# Controller.net
KiCad netlist of a schematic drawn in Altium Designer
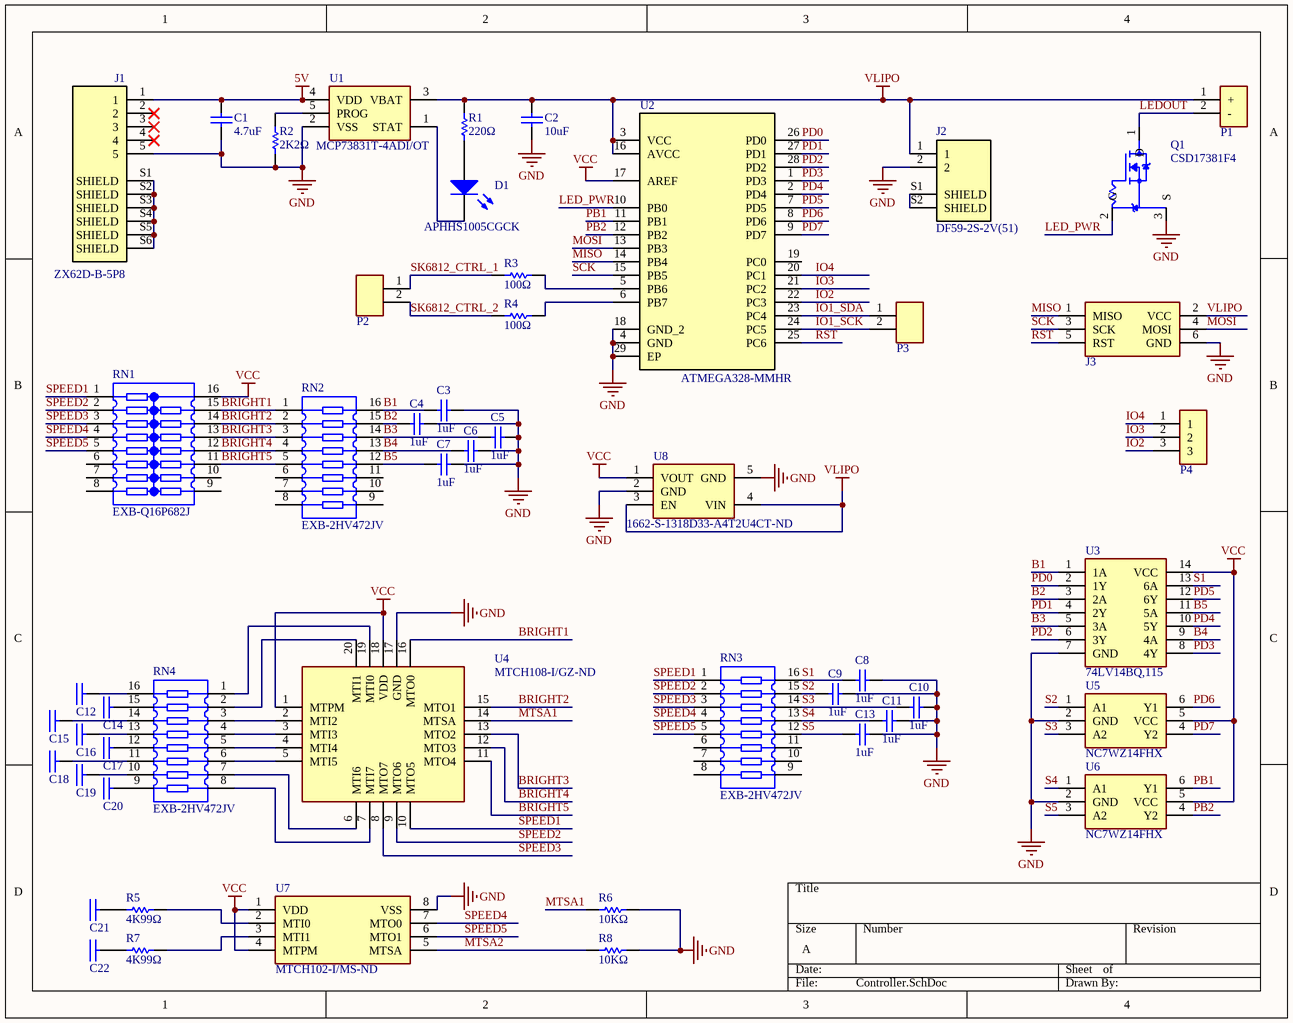
[diagram p0: Controller.SchDoc]

(export (version "E")
  (design (tool "Eeschema 10.0.6"))
  (components
    (comp (ref "C1")
      (value "4.7uF")
      (footprint "0603_CAP")
      (description "CAP CER 4.7UF 25V X5R 0603")
      (fields (field (name "PUBLISHER") "Altium Limited"))
      (libsource (lib "Capacitors_0603") (part "CAP_4U7_0603"))
    )
    (comp (ref "C2")
      (value "10uF")
      (footprint "0603_CAP")
      (description "CAP CER 10UF 10V X5R 0603")
      (fields (field (name "PUBLISHER") "Altium Limited"))
      (libsource (lib "Capacitors_0603") (part "CAP_10U_0603"))
    )
    (comp (ref "C3")
      (value "1uF")
      (footprint "0603_CAP")
      (description "CAP CER 1UF 50V X7R 0603")
      (fields (field (name "PUBLISHER") "Altium Limited"))
      (libsource (lib "Capacitors_0603") (part "CAP_1U_0603"))
    )
    (comp (ref "C4")
      (value "1uF")
      (footprint "0603_CAP")
      (description "CAP CER 1UF 50V X7R 0603")
      (fields (field (name "PUBLISHER") "Altium Limited"))
      (libsource (lib "Capacitors_0603") (part "CAP_1U_0603"))
    )
    (comp (ref "C5")
      (value "1uF")
      (footprint "0603_CAP")
      (description "CAP CER 1UF 50V X7R 0603")
      (fields (field (name "PUBLISHER") "Altium Limited"))
      (libsource (lib "Capacitors_0603") (part "CAP_1U_0603"))
    )
    (comp (ref "C6")
      (value "1uF")
      (footprint "0603_CAP")
      (description "CAP CER 1UF 50V X7R 0603")
      (fields (field (name "PUBLISHER") "Altium Limited"))
      (libsource (lib "Capacitors_0603") (part "CAP_1U_0603"))
    )
    (comp (ref "C7")
      (value "1uF")
      (footprint "0603_CAP")
      (description "CAP CER 1UF 50V X7R 0603")
      (fields (field (name "PUBLISHER") "Altium Limited"))
      (libsource (lib "Capacitors_0603") (part "CAP_1U_0603"))
    )
    (comp (ref "C8")
      (value "1uF")
      (footprint "0603_CAP")
      (description "CAP CER 1UF 50V X7R 0603")
      (fields (field (name "PUBLISHER") "Altium Limited"))
      (libsource (lib "Capacitors_0603") (part "CAP_1U_0603"))
    )
    (comp (ref "C9")
      (value "1uF")
      (footprint "0603_CAP")
      (description "CAP CER 1UF 50V X7R 0603")
      (fields (field (name "PUBLISHER") "Altium Limited"))
      (libsource (lib "Capacitors_0603") (part "CAP_1U_0603"))
    )
    (comp (ref "C10")
      (value "1uF")
      (footprint "0603_CAP")
      (description "CAP CER 1UF 50V X7R 0603")
      (fields (field (name "PUBLISHER") "Altium Limited"))
      (libsource (lib "Capacitors_0603") (part "CAP_1U_0603"))
    )
    (comp (ref "C11")
      (value "1uF")
      (footprint "0603_CAP")
      (description "CAP CER 1UF 50V X7R 0603")
      (fields (field (name "PUBLISHER") "Altium Limited"))
      (libsource (lib "Capacitors_0603") (part "CAP_1U_0603"))
    )
    (comp (ref "C12")
      (value "Human Body Model")
      (footprint "TOUCHSENSE_SLIDE1-END2")
      (description "Touch Sensor Pad, Slide Style 1")
      (fields (field (name "PUBLISHER") "Altium Limited"))
      (libsource (lib "Common Passives") (part "CAP_TOUCH_SLIDE1_END2"))
    )
    (comp (ref "C13")
      (value "1uF")
      (footprint "0603_CAP")
      (description "CAP CER 1UF 50V X7R 0603")
      (fields (field (name "PUBLISHER") "Altium Limited"))
      (libsource (lib "Capacitors_0603") (part "CAP_1U_0603"))
    )
    (comp (ref "C14")
      (value "Human Body Model")
      (footprint "TOUCHSENSE_SLIDE1")
      (description "Touch Sensor Pad, Slide Style 1")
      (fields (field (name "PUBLISHER") "Altium Limited"))
      (libsource (lib "Common Passives") (part "CAP_TOUCH_SLIDE1"))
    )
    (comp (ref "C15")
      (value "Human Body Model")
      (footprint "TOUCHSENSE_SLIDE1")
      (description "Touch Sensor Pad, Slide Style 1")
      (fields (field (name "PUBLISHER") "Altium Limited"))
      (libsource (lib "Common Passives") (part "CAP_TOUCH_SLIDE1"))
    )
    (comp (ref "C16")
      (value "Human Body Model")
      (footprint "TOUCHSENSE_SLIDE1")
      (description "Touch Sensor Pad, Slide Style 1")
      (fields (field (name "PUBLISHER") "Altium Limited"))
      (libsource (lib "Common Passives") (part "CAP_TOUCH_SLIDE1"))
    )
    (comp (ref "C17")
      (value "Human Body Model")
      (footprint "TOUCHSENSE_SLIDE1")
      (description "Touch Sensor Pad, Slide Style 1")
      (fields (field (name "PUBLISHER") "Altium Limited"))
      (libsource (lib "Common Passives") (part "CAP_TOUCH_SLIDE1"))
    )
    (comp (ref "C18")
      (value "Human Body Model")
      (footprint "TOUCHSENSE_SLIDE1")
      (description "Touch Sensor Pad, Slide Style 1")
      (fields (field (name "PUBLISHER") "Altium Limited"))
      (libsource (lib "Common Passives") (part "CAP_TOUCH_SLIDE1"))
    )
    (comp (ref "C19")
      (value "Human Body Model")
      (footprint "TOUCHSENSE_SLIDE1")
      (description "Touch Sensor Pad, Slide Style 1")
      (fields (field (name "PUBLISHER") "Altium Limited"))
      (libsource (lib "Common Passives") (part "CAP_TOUCH_SLIDE1"))
    )
    (comp (ref "C20")
      (value "Human Body Model")
      (footprint "TOUCHSENSE_SLIDE1")
      (description "Touch Sensor Pad, Slide Style 1")
      (fields (field (name "PUBLISHER") "Altium Limited"))
      (libsource (lib "Common Passives") (part "CAP_TOUCH_SLIDE1"))
    )
    (comp (ref "C21")
      (value "Human Body Model")
      (footprint "TOUCHSENSE_SLIDE1")
      (description "Touch Sensor Pad, Slide Style 1")
      (fields (field (name "PUBLISHER") "Altium Limited"))
      (libsource (lib "Common Passives") (part "CAP_TOUCH_SLIDE1"))
    )
    (comp (ref "C22")
      (value "Human Body Model")
      (footprint "TOUCHSENSE_SLIDE1-END1")
      (description "Touch Sensor Pad, Slide Style 1")
      (fields (field (name "PUBLISHER") "Altium Limited"))
      (libsource (lib "Common Passives") (part "CAP_TOUCH_SLIDE1_END1"))
    )
    (comp (ref "D1")
      (value "APHHS1005CGCK")
      (footprint "0402-LED-G")
      (description "LED GREEN CLEAR CHIP SMD")
      (libsource (lib "Diodes") (part "APHHS1005CGCK"))
    )
    (comp (ref "J1")
      (value "ZX62D-B-5P8")
      (footprint "Micro_USB")
      (description "SMD+DIP Micro USB; MICRO-B-SMD")
      (fields (field (name "MF") "Hirose"))
      (libsource (lib "Connectors") (part "MicroUSB"))
    )
    (comp (ref "J2")
      (value "DF59-2S-2V(51)")
      (footprint "SNAPBEE_DF59-2S-2V")
      (description "CONN SSL RCPT 2POS 2MM SOLDER")
      (libsource (lib "Connectors") (part "SNAPBEE_DF59-2S-2V"))
    )
    (comp (ref "J3")
      (value "6 Pin ISP Header")
      (footprint "CONN_ISP_TINY")
      (libsource (lib "Connectors") (part "ISP_TINY"))
    )
    (comp (ref "P1")
      (value "HEADER_1x2_POLAR")
      (footprint "PIN2")
      (description "Polarity")
      (libsource (lib "Connectors") (part "HEADER_1x2_POLAR"))
    )
    (comp (ref "P2")
      (value "HEADER_1x2")
      (footprint "PIN2")
      (libsource (lib "Connectors") (part "HEADER_1x2"))
    )
    (comp (ref "P3") (value "HEADER_1x2") (footprint "PIN2") (libsource (lib "") (part "HEADER_1x2_1")))
    (comp (ref "P4")
      (value "HEADER_1x3")
      (footprint "PIN3")
      (libsource (lib "Connectors") (part "HEADER_1x3"))
    )
    (comp (ref "Q1")
      (value "CSD17381F4")
      (footprint "Common Components:PICOSTAR-3")
      (description "MOSFET N-CH 30V 3.1A 3PICOSTAR")
      (fields (field (name "MF") "{'manufacturer': u'Texas Instruments'}"))
      (libsource (lib "Transistors") (part "CSD17381F4"))
    )
    (comp (ref "R1")
      (value "220Ω")
      (footprint "0603_RES")
      (description "RES SMD 220 OHM 1% 1/10W 0603")
      (fields (field (name "PUBLISHER") "Altium Limited"))
      (libsource (lib "Resistors_0603") (part "RES_220R_0603"))
    )
    (comp (ref "R2")
      (value "2K2Ω")
      (footprint "0603_RES")
      (description "RES SMD 2.2K OHM 1% 1/10W 0603")
      (fields (field (name "PUBLISHER") "Altium Limited"))
      (libsource (lib "Resistors_0603") (part "RES_2K2_0603"))
    )
    (comp (ref "R3")
      (value "100Ω")
      (footprint "0603_RES")
      (description "RES SMD 100 OHM 1% 1/10W 0603")
      (fields (field (name "PUBLISHER") "Altium Limited"))
      (libsource (lib "Resistors_0603") (part "RES_100R_0603"))
    )
    (comp (ref "R4")
      (value "100Ω")
      (footprint "0603_RES")
      (description "RES SMD 100 OHM 1% 1/10W 0603")
      (fields (field (name "PUBLISHER") "Altium Limited"))
      (libsource (lib "Resistors_0603") (part "RES_100R_0603"))
    )
    (comp (ref "R5")
      (value "4K99Ω")
      (footprint "0603_RES")
      (description "RES SMD 4.99K OHM 1% 1/10W 0603")
      (fields (field (name "PUBLISHER") "Altium Limited"))
      (libsource (lib "Resistors_0603") (part "RES_4K99_0603"))
    )
    (comp (ref "R6")
      (value "10KΩ")
      (footprint "0603_RES")
      (description "RES SMD 10K OHM 1% 1/10W 0603")
      (fields (field (name "PUBLISHER") "Altium Limited"))
      (libsource (lib "Resistors_0603") (part "RES_10K_0603"))
    )
    (comp (ref "R7")
      (value "4K99Ω")
      (footprint "0603_RES")
      (description "RES SMD 4.99K OHM 1% 1/10W 0603")
      (fields (field (name "PUBLISHER") "Altium Limited"))
      (libsource (lib "Resistors_0603") (part "RES_4K99_0603"))
    )
    (comp (ref "R8")
      (value "10KΩ")
      (footprint "0603_RES")
      (description "RES SMD 10K OHM 1% 1/10W 0603")
      (fields (field (name "PUBLISHER") "Altium Limited"))
      (libsource (lib "Resistors_0603") (part "RES_10K_0603"))
    )
    (comp (ref "RN1")
      (value "EXB-Q16P682J")
      (footprint "Common Components:RES-ARRAY-16_EXB")
      (description "RES ARRAY 15 RES 6.8K OHM 1506")
      (fields (field (name "MF") "{'manufacturer': u'Panasonic'}"))
      (libsource (lib "Common Passives") (part "EXB-Q16P682J"))
    )
    (comp (ref "RN2")
      (value "EXB-2HV472JV")
      (footprint "Common Components:RES-ARRAY-16_EXB")
      (description "RES ARRAY 8 RES 4.7K OHM 1506")
      (fields (field (name "MF") "{'manufacturer': u'Panasonic'}") (field (name "MP") "EXB-Q16P682J"))
      (libsource (lib "Common Passives") (part "EXB-2HV472JV"))
    )
    (comp (ref "RN3")
      (value "EXB-2HV472JV")
      (footprint "Common Components:RES-ARRAY-16_EXB")
      (description "RES ARRAY 8 RES 4.7K OHM 1506")
      (fields (field (name "MF") "{'manufacturer': u'Panasonic'}") (field (name "MP") "EXB-Q16P682J"))
      (libsource (lib "Common Passives") (part "EXB-2HV472JV"))
    )
    (comp (ref "RN4")
      (value "EXB-2HV472JV")
      (footprint "Common Components:RES-ARRAY-16_EXB")
      (description "RES ARRAY 8 RES 4.7K OHM 1506")
      (fields (field (name "MF") "{'manufacturer': u'Panasonic'}") (field (name "MP") "EXB-Q16P682J"))
      (libsource (lib "") (part "EXB-2HV472JV_1"))
    )
    (comp (ref "U1")
      (value "MCP73831T-4ADI/OT")
      (footprint "Common Components:SOT-23-5-N")
      (description "IC BATT CNTL LI-ION 1CEL SOT23-5")
      (fields (field (name "MF") "{'manufacturer': u'Microchip'}"))
      (libsource (lib "Common ICs") (part "MCP73831T-4ADI/OT"))
    )
    (comp (ref "U2")
      (value "ATMEGA328-MMHR")
      (footprint "Common Components:QFN-28_4x4")
      (description "IC MCU 8BIT 32KB FLASH 28VQFN")
      (fields (field (name "MF") "Microchip") (field (name "MP") "ATMEGA328P-PU"))
      (libsource (lib "Microcontrollers") (part "ATMEGA328-MMHR"))
    )
    (comp (ref "U3")
      (value "74LV14BQ,115")
      (footprint "DHVQFN-14")
      (description "IC INVERTER 6CH 6-INP 14DHVQFN")
      (libsource (lib "74xxChips") (part "74LV14BQ,115"))
    )
    (comp (ref "U4")
      (value "MTCH108-I/GZ")
      (footprint "UQFN-20_4x4")
      (description "IC PROXIMITY DETECTOR 20UQFN")
      (fields (field (name "SUPPLIER PART NUMBER 1") "MTCH108-I/GZ-ND"))
      (libsource (lib "Common ICs") (part "MTCH108-I/GZ"))
    )
    (comp (ref "U5")
      (value "NC7WZ14FHX")
      (footprint "MICROPAK2")
      (description "IC INVERTER 2CH 2-INP 6MICROPAK2")
      (libsource (lib "74xxChips") (part "NC7WZ14FHX"))
    )
    (comp (ref "U6")
      (value "NC7WZ14FHX")
      (footprint "MICROPAK2")
      (description "IC INVERTER 2CH 2-INP 6MICROPAK2")
      (libsource (lib "74xxChips") (part "NC7WZ14FHX"))
    )
    (comp (ref "U7")
      (value "MTCH102-I/MS")
      (footprint "MSOP-8")
      (description "IC PROXIMITY DETECTOR 8MSOP")
      (fields (field (name "SUPPLIER PART NUMBER 1") "MTCH102-I/MS-ND"))
      (libsource (lib "Common ICs") (part "MTCH102-I/MS"))
    )
    (comp (ref "U8")
      (value "S-1318D33-A4T2U4")
      (footprint "HSNT-4-B")
      (description "IC REG LINEAR 3.3V 100MA HSNT4-B")
      (fields (field (name "SUPPLIER PART NUMBER 1") "1662-S-1318D33-A4T2U4CT-ND"))
      (libsource (lib "Common ICs") (part "S-1318D33-A4T2U4"))
    )
  )
  (nets
    (net (code "1") (name "/B1") (class "Default")
      (node (ref "C3") (pin "2") (pinfunction "2_2") (pintype "passive"))
      (node (ref "RN2") (pin "16") (pinfunction "16_16") (pintype "passive"))
      (node (ref "U3") (pin "1") (pinfunction "1A_1") (pintype "passive"))
    )
    (net (code "2") (name "/B2") (class "Default")
      (node (ref "C4") (pin "2") (pinfunction "2_2") (pintype "passive"))
      (node (ref "RN2") (pin "15") (pinfunction "15_15") (pintype "passive"))
      (node (ref "U3") (pin "3") (pinfunction "2A_3") (pintype "passive"))
    )
    (net (code "3") (name "/B3") (class "Default")
      (node (ref "C5") (pin "2") (pinfunction "2_2") (pintype "passive"))
      (node (ref "RN2") (pin "14") (pinfunction "14_14") (pintype "passive"))
      (node (ref "U3") (pin "5") (pinfunction "3A_5") (pintype "passive"))
    )
    (net (code "4") (name "/B4") (class "Default")
      (node (ref "C6") (pin "2") (pinfunction "2_2") (pintype "passive"))
      (node (ref "RN2") (pin "13") (pinfunction "13_13") (pintype "passive"))
      (node (ref "U3") (pin "9") (pinfunction "4A_9") (pintype "passive"))
    )
    (net (code "5") (name "/B5") (class "Default")
      (node (ref "C7") (pin "1") (pinfunction "1_1") (pintype "passive"))
      (node (ref "RN2") (pin "12") (pinfunction "12_12") (pintype "passive"))
      (node (ref "U3") (pin "11") (pinfunction "5A_11") (pintype "passive"))
    )
    (net (code "6") (name "/BRIGHT1") (class "Default")
      (node (ref "RN1") (pin "15") (pinfunction "15_15") (pintype "passive"))
      (node (ref "RN2") (pin "1") (pinfunction "1_1") (pintype "passive"))
      (node (ref "U4") (pin "16") (pinfunction "MTO0_16") (pintype "passive"))
    )
    (net (code "7") (name "/BRIGHT2") (class "Default")
      (node (ref "RN1") (pin "14") (pinfunction "14_14") (pintype "passive"))
      (node (ref "RN2") (pin "2") (pinfunction "2_2") (pintype "passive"))
      (node (ref "U4") (pin "15") (pinfunction "MTO1_15") (pintype "passive"))
    )
    (net (code "8") (name "/BRIGHT3") (class "Default")
      (node (ref "RN1") (pin "13") (pinfunction "13_13") (pintype "passive"))
      (node (ref "RN2") (pin "3") (pinfunction "3_3") (pintype "passive"))
      (node (ref "U4") (pin "13") (pinfunction "MTO2_13") (pintype "passive"))
    )
    (net (code "9") (name "/BRIGHT4") (class "Default")
      (node (ref "RN1") (pin "12") (pinfunction "12_12") (pintype "passive"))
      (node (ref "RN2") (pin "4") (pinfunction "4_4") (pintype "passive"))
      (node (ref "U4") (pin "12") (pinfunction "MTO3_12") (pintype "passive"))
    )
    (net (code "10") (name "/BRIGHT5") (class "Default")
      (node (ref "RN1") (pin "11") (pinfunction "11_11") (pintype "passive"))
      (node (ref "RN2") (pin "5") (pinfunction "5_5") (pintype "passive"))
      (node (ref "U4") (pin "11") (pinfunction "MTO4_11") (pintype "passive"))
    )
    (net (code "11") (name "/IO1_SCK") (class "Default")
      (node (ref "P3") (pin "2") (pinfunction "-_2") (pintype "passive"))
      (node (ref "U2") (pin "24") (pinfunction "PC5_24") (pintype "passive"))
    )
    (net (code "12") (name "/IO1_SDA") (class "Default")
      (node (ref "P3") (pin "1") (pinfunction "+_1") (pintype "passive"))
      (node (ref "U2") (pin "23") (pinfunction "PC4_23") (pintype "passive"))
    )
    (net (code "13") (name "/IO2") (class "Default")
      (node (ref "P4") (pin "3") (pinfunction "3_3") (pintype "passive"))
      (node (ref "U2") (pin "22") (pinfunction "PC3_22") (pintype "passive"))
    )
    (net (code "14") (name "/IO3") (class "Default")
      (node (ref "P4") (pin "2") (pinfunction "2_2") (pintype "passive"))
      (node (ref "U2") (pin "21") (pinfunction "PC2_21") (pintype "passive"))
    )
    (net (code "15") (name "/IO4") (class "Default")
      (node (ref "P4") (pin "1") (pinfunction "1_1") (pintype "passive"))
      (node (ref "U2") (pin "20") (pinfunction "PC1_20") (pintype "passive"))
    )
    (net (code "16") (name "/LEDOUT") (class "Default")
      (node (ref "P1") (pin "2") (pinfunction "-_2") (pintype "passive"))
      (node (ref "Q1") (pin "1") (pinfunction "D_1") (pintype "passive"))
    )
    (net (code "17") (name "/LED_PWR") (class "Default")
      (node (ref "Q1") (pin "2") (pinfunction "G_2") (pintype "passive"))
      (node (ref "U2") (pin "10") (pinfunction "PB0_10") (pintype "passive"))
    )
    (net (code "18") (name "/MISO") (class "Default")
      (node (ref "J3") (pin "1") (pinfunction "MISO_1") (pintype "passive"))
      (node (ref "U2") (pin "14") (pinfunction "PB4_14") (pintype "passive"))
    )
    (net (code "19") (name "/MOSI") (class "Default")
      (node (ref "J3") (pin "4") (pinfunction "MOSI_4") (pintype "passive"))
      (node (ref "U2") (pin "13") (pinfunction "PB3_13") (pintype "passive"))
    )
    (net (code "20") (name "/MTSA1") (class "Default")
      (node (ref "R6") (pin "2") (pinfunction "2_2") (pintype "passive"))
      (node (ref "U4") (pin "14") (pinfunction "MTSA_14") (pintype "passive"))
    )
    (net (code "21") (name "/MTSA2") (class "Default")
      (node (ref "R8") (pin "1") (pinfunction "1_1") (pintype "passive"))
      (node (ref "U7") (pin "5") (pinfunction "MTSA_5") (pintype "passive"))
    )
    (net (code "22") (name "/PB1") (class "Default")
      (node (ref "U2") (pin "11") (pinfunction "PB1_11") (pintype "passive"))
      (node (ref "U6") (pin "6") (pinfunction "Y1_6") (pintype "passive"))
    )
    (net (code "23") (name "/PB2") (class "Default")
      (node (ref "U2") (pin "12") (pinfunction "PB2_12") (pintype "passive"))
      (node (ref "U6") (pin "4") (pinfunction "Y2_4") (pintype "passive"))
    )
    (net (code "24") (name "/PD0") (class "Default")
      (node (ref "U2") (pin "26") (pinfunction "PD0_26") (pintype "passive"))
      (node (ref "U3") (pin "2") (pinfunction "1Y_2") (pintype "passive"))
    )
    (net (code "25") (name "/PD1") (class "Default")
      (node (ref "U2") (pin "27") (pinfunction "PD1_27") (pintype "passive"))
      (node (ref "U3") (pin "4") (pinfunction "2Y_4") (pintype "passive"))
    )
    (net (code "26") (name "/PD2") (class "Default")
      (node (ref "U2") (pin "28") (pinfunction "PD2_28") (pintype "passive"))
      (node (ref "U3") (pin "6") (pinfunction "3Y_6") (pintype "passive"))
    )
    (net (code "27") (name "/PD3") (class "Default")
      (node (ref "U2") (pin "1") (pinfunction "PD3_1") (pintype "passive"))
      (node (ref "U3") (pin "8") (pinfunction "4Y_8") (pintype "passive"))
    )
    (net (code "28") (name "/PD4") (class "Default")
      (node (ref "U2") (pin "2") (pinfunction "PD4_2") (pintype "passive"))
      (node (ref "U3") (pin "10") (pinfunction "5Y_10") (pintype "passive"))
    )
    (net (code "29") (name "/PD5") (class "Default")
      (node (ref "U2") (pin "7") (pinfunction "PD5_7") (pintype "passive"))
      (node (ref "U3") (pin "12") (pinfunction "6Y_12") (pintype "passive"))
    )
    (net (code "30") (name "/PD6") (class "Default")
      (node (ref "U2") (pin "8") (pinfunction "PD6_8") (pintype "passive"))
      (node (ref "U5") (pin "6") (pinfunction "Y1_6") (pintype "passive"))
    )
    (net (code "31") (name "/PD7") (class "Default")
      (node (ref "U2") (pin "9") (pinfunction "PD7_9") (pintype "passive"))
      (node (ref "U5") (pin "4") (pinfunction "Y2_4") (pintype "passive"))
    )
    (net (code "32") (name "/RST") (class "Default")
      (node (ref "J3") (pin "5") (pinfunction "RST_5") (pintype "passive"))
      (node (ref "U2") (pin "25") (pinfunction "PC6_25") (pintype "passive"))
    )
    (net (code "33") (name "/S1") (class "Default")
      (node (ref "C8") (pin "2") (pinfunction "2_2") (pintype "passive"))
      (node (ref "RN3") (pin "16") (pinfunction "16_16") (pintype "passive"))
      (node (ref "U3") (pin "13") (pinfunction "6A_13") (pintype "passive"))
    )
    (net (code "34") (name "/S2") (class "Default")
      (node (ref "C9") (pin "2") (pinfunction "2_2") (pintype "passive"))
      (node (ref "RN3") (pin "15") (pinfunction "15_15") (pintype "passive"))
      (node (ref "U5") (pin "1") (pinfunction "A1_1") (pintype "passive"))
    )
    (net (code "35") (name "/S3") (class "Default")
      (node (ref "C10") (pin "2") (pinfunction "2_2") (pintype "passive"))
      (node (ref "RN3") (pin "14") (pinfunction "14_14") (pintype "passive"))
      (node (ref "U5") (pin "3") (pinfunction "A2_3") (pintype "passive"))
    )
    (net (code "36") (name "/S4") (class "Default")
      (node (ref "C11") (pin "2") (pinfunction "2_2") (pintype "passive"))
      (node (ref "RN3") (pin "13") (pinfunction "13_13") (pintype "passive"))
      (node (ref "U6") (pin "1") (pinfunction "A1_1") (pintype "passive"))
    )
    (net (code "37") (name "/S5") (class "Default")
      (node (ref "C13") (pin "1") (pinfunction "1_1") (pintype "passive"))
      (node (ref "RN3") (pin "12") (pinfunction "12_12") (pintype "passive"))
      (node (ref "U6") (pin "3") (pinfunction "A2_3") (pintype "passive"))
    )
    (net (code "38") (name "/SCK") (class "Default")
      (node (ref "J3") (pin "3") (pinfunction "SCK_3") (pintype "passive"))
      (node (ref "U2") (pin "15") (pinfunction "PB5_15") (pintype "passive"))
    )
    (net (code "39") (name "/SK6812_CTRL_1") (class "Default")
      (node (ref "P2") (pin "1") (pinfunction "+_1") (pintype "passive"))
      (node (ref "R3") (pin "1") (pinfunction "1_1") (pintype "passive"))
    )
    (net (code "40") (name "/SK6812_CTRL_2") (class "Default")
      (node (ref "P2") (pin "2") (pinfunction "-_2") (pintype "passive"))
      (node (ref "R4") (pin "1") (pinfunction "1_1") (pintype "passive"))
    )
    (net (code "41") (name "/SPEED1") (class "Default")
      (node (ref "RN1") (pin "1") (pinfunction "1_1") (pintype "passive"))
      (node (ref "RN3") (pin "1") (pinfunction "1_1") (pintype "passive"))
      (node (ref "U4") (pin "10") (pinfunction "MTO5_10") (pintype "passive"))
    )
    (net (code "42") (name "/SPEED2") (class "Default")
      (node (ref "RN1") (pin "2") (pinfunction "2_2") (pintype "passive"))
      (node (ref "RN3") (pin "2") (pinfunction "2_2") (pintype "passive"))
      (node (ref "U4") (pin "9") (pinfunction "MTO6_9") (pintype "passive"))
    )
    (net (code "43") (name "/SPEED3") (class "Default")
      (node (ref "RN1") (pin "3") (pinfunction "3_3") (pintype "passive"))
      (node (ref "RN3") (pin "3") (pinfunction "3_3") (pintype "passive"))
      (node (ref "U4") (pin "8") (pinfunction "MTO7_8") (pintype "passive"))
    )
    (net (code "44") (name "/SPEED4") (class "Default")
      (node (ref "RN1") (pin "4") (pinfunction "4_4") (pintype "passive"))
      (node (ref "RN3") (pin "4") (pinfunction "4_4") (pintype "passive"))
      (node (ref "U7") (pin "7") (pinfunction "MTO0_7") (pintype "passive"))
    )
    (net (code "45") (name "/SPEED5") (class "Default")
      (node (ref "RN1") (pin "5") (pinfunction "5_5") (pintype "passive"))
      (node (ref "RN3") (pin "5") (pinfunction "5_5") (pintype "passive"))
      (node (ref "U7") (pin "6") (pinfunction "MTO1_6") (pintype "passive"))
    )
    (net (code "46") (name "5V") (class "Default")
      (node (ref "C1") (pin "2") (pinfunction "2_2") (pintype "passive"))
      (node (ref "J1") (pin "1") (pinfunction "1_1") (pintype "power_in"))
      (node (ref "U1") (pin "4") (pinfunction "VDD_4") (pintype "passive"))
    )
    (net (code "47") (name "GND") (class "Default")
      (node (ref "C1") (pin "1") (pinfunction "1_1") (pintype "passive"))
      (node (ref "C10") (pin "1") (pinfunction "1_1") (pintype "passive"))
      (node (ref "C11") (pin "1") (pinfunction "1_1") (pintype "passive"))
      (node (ref "C13") (pin "2") (pinfunction "2_2") (pintype "passive"))
      (node (ref "C2") (pin "1") (pinfunction "1_1") (pintype "passive"))
      (node (ref "C3") (pin "1") (pinfunction "1_1") (pintype "passive"))
      (node (ref "C4") (pin "1") (pinfunction "1_1") (pintype "passive"))
      (node (ref "C5") (pin "1") (pinfunction "1_1") (pintype "passive"))
      (node (ref "C6") (pin "1") (pinfunction "1_1") (pintype "passive"))
      (node (ref "C7") (pin "2") (pinfunction "2_2") (pintype "passive"))
      (node (ref "C8") (pin "1") (pinfunction "1_1") (pintype "passive"))
      (node (ref "C9") (pin "1") (pinfunction "1_1") (pintype "passive"))
      (node (ref "J1") (pin "5") (pinfunction "5_5") (pintype "passive"))
      (node (ref "J2") (pin "2") (pinfunction "2_2") (pintype "passive"))
      (node (ref "J3") (pin "6") (pinfunction "GND_6") (pintype "passive"))
      (node (ref "Q1") (pin "3") (pinfunction "S_3") (pintype "passive"))
      (node (ref "R2") (pin "1") (pinfunction "1_1") (pintype "passive"))
      (node (ref "R6") (pin "1") (pinfunction "1_1") (pintype "passive"))
      (node (ref "R8") (pin "2") (pinfunction "2_2") (pintype "passive"))
      (node (ref "U1") (pin "2") (pinfunction "VSS_2") (pintype "passive"))
      (node (ref "U2") (pin "18") (pinfunction "GND_2_18") (pintype "passive"))
      (node (ref "U2") (pin "29") (pinfunction "EP_29") (pintype "passive"))
      (node (ref "U2") (pin "4") (pinfunction "GND_4") (pintype "passive"))
      (node (ref "U3") (pin "7") (pinfunction "GND_7") (pintype "passive"))
      (node (ref "U4") (pin "17") (pinfunction "GND_17") (pintype "passive"))
      (node (ref "U5") (pin "2") (pinfunction "GND_2") (pintype "passive"))
      (node (ref "U6") (pin "2") (pinfunction "GND_2") (pintype "passive"))
      (node (ref "U7") (pin "8") (pinfunction "VSS_8") (pintype "passive"))
      (node (ref "U8") (pin "2") (pinfunction "GND_2") (pintype "passive"))
      (node (ref "U8") (pin "5") (pinfunction "GND_5") (pintype "passive"))
    )
    (net (code "48") (name "Net-(C12-Pad1)") (class "Default")
      (node (ref "C12") (pin "1") (pinfunction "1_1") (pintype "passive"))
      (node (ref "RN4") (pin "16") (pinfunction "16_16") (pintype "passive"))
    )
    (net (code "49") (name "Net-(C14-Pad1)") (class "Default")
      (node (ref "C14") (pin "1") (pinfunction "1_1") (pintype "passive"))
      (node (ref "RN4") (pin "15") (pinfunction "15_15") (pintype "passive"))
    )
    (net (code "50") (name "Net-(C15-Pad1)") (class "Default")
      (node (ref "C15") (pin "1") (pinfunction "1_1") (pintype "passive"))
      (node (ref "RN4") (pin "14") (pinfunction "14_14") (pintype "passive"))
    )
    (net (code "51") (name "Net-(C16-Pad1)") (class "Default")
      (node (ref "C16") (pin "1") (pinfunction "1_1") (pintype "passive"))
      (node (ref "RN4") (pin "13") (pinfunction "13_13") (pintype "passive"))
    )
    (net (code "52") (name "Net-(C17-Pad1)") (class "Default")
      (node (ref "C17") (pin "1") (pinfunction "1_1") (pintype "passive"))
      (node (ref "RN4") (pin "12") (pinfunction "12_12") (pintype "passive"))
    )
    (net (code "53") (name "Net-(C18-Pad1)") (class "Default")
      (node (ref "C18") (pin "1") (pinfunction "1_1") (pintype "passive"))
      (node (ref "RN4") (pin "11") (pinfunction "11_11") (pintype "passive"))
    )
    (net (code "54") (name "Net-(C19-Pad1)") (class "Default")
      (node (ref "C19") (pin "1") (pinfunction "1_1") (pintype "passive"))
      (node (ref "RN4") (pin "10") (pinfunction "10_10") (pintype "passive"))
    )
    (net (code "55") (name "Net-(C20-Pad1)") (class "Default")
      (node (ref "C20") (pin "1") (pinfunction "1_1") (pintype "passive"))
      (node (ref "RN4") (pin "9") (pinfunction "9_9") (pintype "passive"))
    )
    (net (code "56") (name "Net-(C21-Pad1)") (class "Default")
      (node (ref "C21") (pin "1") (pinfunction "1_1") (pintype "passive"))
      (node (ref "R5") (pin "1") (pinfunction "1_1") (pintype "passive"))
    )
    (net (code "57") (name "Net-(C22-Pad1)") (class "Default")
      (node (ref "C22") (pin "1") (pinfunction "1_1") (pintype "passive"))
      (node (ref "R7") (pin "1") (pinfunction "1_1") (pintype "passive"))
    )
    (net (code "58") (name "Net-(D1-A)") (class "Default")
      (node (ref "D1") (pin "2") (pinfunction "A_2") (pintype "passive"))
      (node (ref "R1") (pin "1") (pinfunction "1_1") (pintype "passive"))
    )
    (net (code "59") (name "Net-(D1-K)") (class "Default")
      (node (ref "D1") (pin "1") (pinfunction "K_1") (pintype "passive"))
      (node (ref "U1") (pin "1") (pinfunction "STAT_1") (pintype "passive"))
    )
    (net (code "60") (name "Net-(J1-SHIELD-PadS1)") (class "Default")
      (node (ref "J1") (pin "S1") (pinfunction "SHIELD_S1") (pintype "passive"))
      (node (ref "J1") (pin "S2") (pinfunction "SHIELD_S2") (pintype "passive"))
      (node (ref "J1") (pin "S3") (pinfunction "SHIELD_S3") (pintype "passive"))
      (node (ref "J1") (pin "S4") (pinfunction "SHIELD_S4") (pintype "passive"))
      (node (ref "J1") (pin "S5") (pinfunction "SHIELD_S5") (pintype "passive"))
      (node (ref "J1") (pin "S6") (pinfunction "SHIELD_S6") (pintype "passive"))
    )
    (net (code "61") (name "Net-(J2-SHIELD-PadS1)") (class "Default")
      (node (ref "J2") (pin "S1") (pinfunction "SHIELD_S1") (pintype "passive"))
      (node (ref "J2") (pin "S2") (pinfunction "SHIELD_S2") (pintype "passive"))
    )
    (net (code "62") (name "Net-(U1-PROG)") (class "Default")
      (node (ref "R2") (pin "2") (pinfunction "2_2") (pintype "passive"))
      (node (ref "U1") (pin "5") (pinfunction "PROG_5") (pintype "passive"))
    )
    (net (code "63") (name "Net-(U2-PB6)") (class "Default")
      (node (ref "R3") (pin "2") (pinfunction "2_2") (pintype "passive"))
      (node (ref "U2") (pin "5") (pinfunction "PB6_5") (pintype "passive"))
    )
    (net (code "64") (name "Net-(U2-PB7)") (class "Default")
      (node (ref "R4") (pin "2") (pinfunction "2_2") (pintype "passive"))
      (node (ref "U2") (pin "6") (pinfunction "PB7_6") (pintype "passive"))
    )
    (net (code "65") (name "Net-(U4-MTI0)") (class "Default")
      (node (ref "RN4") (pin "1") (pinfunction "1_1") (pintype "passive"))
      (node (ref "U4") (pin "19") (pinfunction "MTI0_19") (pintype "passive"))
    )
    (net (code "66") (name "Net-(U4-MTI1)") (class "Default")
      (node (ref "RN4") (pin "2") (pinfunction "2_2") (pintype "passive"))
      (node (ref "U4") (pin "20") (pinfunction "MTI1_20") (pintype "passive"))
    )
    (net (code "67") (name "Net-(U4-MTI2)") (class "Default")
      (node (ref "RN4") (pin "3") (pinfunction "3_3") (pintype "passive"))
      (node (ref "U4") (pin "2") (pinfunction "MTI2_2") (pintype "passive"))
    )
    (net (code "68") (name "Net-(U4-MTI3)") (class "Default")
      (node (ref "RN4") (pin "4") (pinfunction "4_4") (pintype "passive"))
      (node (ref "U4") (pin "3") (pinfunction "MTI3_3") (pintype "passive"))
    )
    (net (code "69") (name "Net-(U4-MTI4)") (class "Default")
      (node (ref "RN4") (pin "5") (pinfunction "5_5") (pintype "passive"))
      (node (ref "U4") (pin "4") (pinfunction "MTI4_4") (pintype "passive"))
    )
    (net (code "70") (name "Net-(U4-MTI5)") (class "Default")
      (node (ref "RN4") (pin "6") (pinfunction "6_6") (pintype "passive"))
      (node (ref "U4") (pin "5") (pinfunction "MTI5_5") (pintype "passive"))
    )
    (net (code "71") (name "Net-(U4-MTI6)") (class "Default")
      (node (ref "RN4") (pin "7") (pinfunction "7_7") (pintype "passive"))
      (node (ref "U4") (pin "6") (pinfunction "MTI6_6") (pintype "passive"))
    )
    (net (code "72") (name "Net-(U4-MTI7)") (class "Default")
      (node (ref "RN4") (pin "8") (pinfunction "8_8") (pintype "passive"))
      (node (ref "U4") (pin "7") (pinfunction "MTI7_7") (pintype "passive"))
    )
    (net (code "73") (name "Net-(U7-MTI0)") (class "Default")
      (node (ref "R5") (pin "2") (pinfunction "2_2") (pintype "passive"))
      (node (ref "U7") (pin "2") (pinfunction "MTI0_2") (pintype "passive"))
    )
    (net (code "74") (name "Net-(U7-MTI1)") (class "Default")
      (node (ref "R7") (pin "2") (pinfunction "2_2") (pintype "passive"))
      (node (ref "U7") (pin "3") (pinfunction "MTI1_3") (pintype "passive"))
    )
    (net (code "75") (name "VCC") (class "Default")
      (node (ref "RN1") (pin "16") (pinfunction "16_16") (pintype "passive"))
      (node (ref "U2") (pin "17") (pinfunction "AREF_17") (pintype "passive"))
      (node (ref "U3") (pin "14") (pinfunction "VCC_14") (pintype "passive"))
      (node (ref "U4") (pin "1") (pinfunction "MTPM_1") (pintype "passive"))
      (node (ref "U4") (pin "18") (pinfunction "VDD_18") (pintype "passive"))
      (node (ref "U5") (pin "5") (pinfunction "VCC_5") (pintype "passive"))
      (node (ref "U6") (pin "5") (pinfunction "VCC_5") (pintype "passive"))
      (node (ref "U7") (pin "1") (pinfunction "VDD_1") (pintype "passive"))
      (node (ref "U7") (pin "4") (pinfunction "MTPM_4") (pintype "passive"))
      (node (ref "U8") (pin "1") (pinfunction "VOUT_1") (pintype "passive"))
    )
    (net (code "76") (name "VLIPO") (class "Default")
      (node (ref "C2") (pin "2") (pinfunction "2_2") (pintype "passive"))
      (node (ref "J2") (pin "1") (pinfunction "1_1") (pintype "power_in"))
      (node (ref "J3") (pin "2") (pinfunction "VCC_2") (pintype "passive"))
      (node (ref "P1") (pin "1") (pinfunction "+_1") (pintype "passive"))
      (node (ref "R1") (pin "2") (pinfunction "2_2") (pintype "passive"))
      (node (ref "U1") (pin "3") (pinfunction "VBAT_3") (pintype "passive"))
      (node (ref "U2") (pin "16") (pinfunction "AVCC_16") (pintype "power_in"))
      (node (ref "U2") (pin "3") (pinfunction "VCC_3") (pintype "power_in"))
      (node (ref "U8") (pin "3") (pinfunction "EN_3") (pintype "passive"))
      (node (ref "U8") (pin "4") (pinfunction "VIN_4") (pintype "passive"))
    )
    (net (code "77") (name "unconnected-(J1-Pad2)") (class "Default")
      (node (ref "J1") (pin "2") (pinfunction "2_2") (pintype "passive+no_connect"))
    )
    (net (code "78") (name "unconnected-(J1-Pad3)") (class "Default")
      (node (ref "J1") (pin "3") (pinfunction "3_3") (pintype "passive+no_connect"))
    )
    (net (code "79") (name "unconnected-(J1-Pad4)") (class "Default")
      (node (ref "J1") (pin "4") (pinfunction "4_4") (pintype "passive+no_connect"))
    )
    (net (code "80") (name "unconnected-(RN1-Pad6)") (class "Default")
      (node (ref "RN1") (pin "6") (pinfunction "6_6") (pintype "passive"))
    )
    (net (code "81") (name "unconnected-(RN1-Pad7)") (class "Default")
      (node (ref "RN1") (pin "7") (pinfunction "7_7") (pintype "passive"))
    )
    (net (code "82") (name "unconnected-(RN1-Pad8)") (class "Default")
      (node (ref "RN1") (pin "8") (pinfunction "8_8") (pintype "passive"))
    )
    (net (code "83") (name "unconnected-(RN1-Pad9)") (class "Default")
      (node (ref "RN1") (pin "9") (pinfunction "9_9") (pintype "passive"))
    )
    (net (code "84") (name "unconnected-(RN1-Pad10)") (class "Default")
      (node (ref "RN1") (pin "10") (pinfunction "10_10") (pintype "passive"))
    )
    (net (code "85") (name "unconnected-(RN2-Pad6)") (class "Default")
      (node (ref "RN2") (pin "6") (pinfunction "6_6") (pintype "passive"))
    )
    (net (code "86") (name "unconnected-(RN2-Pad7)") (class "Default")
      (node (ref "RN2") (pin "7") (pinfunction "7_7") (pintype "passive"))
    )
    (net (code "87") (name "unconnected-(RN2-Pad8)") (class "Default")
      (node (ref "RN2") (pin "8") (pinfunction "8_8") (pintype "passive"))
    )
    (net (code "88") (name "unconnected-(RN2-Pad9)") (class "Default")
      (node (ref "RN2") (pin "9") (pinfunction "9_9") (pintype "passive"))
    )
    (net (code "89") (name "unconnected-(RN2-Pad10)") (class "Default")
      (node (ref "RN2") (pin "10") (pinfunction "10_10") (pintype "passive"))
    )
    (net (code "90") (name "unconnected-(RN2-Pad11)") (class "Default")
      (node (ref "RN2") (pin "11") (pinfunction "11_11") (pintype "passive"))
    )
    (net (code "91") (name "unconnected-(RN3-Pad6)") (class "Default")
      (node (ref "RN3") (pin "6") (pinfunction "6_6") (pintype "passive"))
    )
    (net (code "92") (name "unconnected-(RN3-Pad7)") (class "Default")
      (node (ref "RN3") (pin "7") (pinfunction "7_7") (pintype "passive"))
    )
    (net (code "93") (name "unconnected-(RN3-Pad8)") (class "Default")
      (node (ref "RN3") (pin "8") (pinfunction "8_8") (pintype "passive"))
    )
    (net (code "94") (name "unconnected-(RN3-Pad9)") (class "Default")
      (node (ref "RN3") (pin "9") (pinfunction "9_9") (pintype "passive"))
    )
    (net (code "95") (name "unconnected-(RN3-Pad10)") (class "Default")
      (node (ref "RN3") (pin "10") (pinfunction "10_10") (pintype "passive"))
    )
    (net (code "96") (name "unconnected-(RN3-Pad11)") (class "Default")
      (node (ref "RN3") (pin "11") (pinfunction "11_11") (pintype "passive"))
    )
    (net (code "97") (name "unconnected-(U2-PC0-Pad19)") (class "Default")
      (node (ref "U2") (pin "19") (pinfunction "PC0_19") (pintype "passive"))
    )
  )
)
